# MPU_12x12.net
KiCad netlist of a schematic drawn in Altium Designer
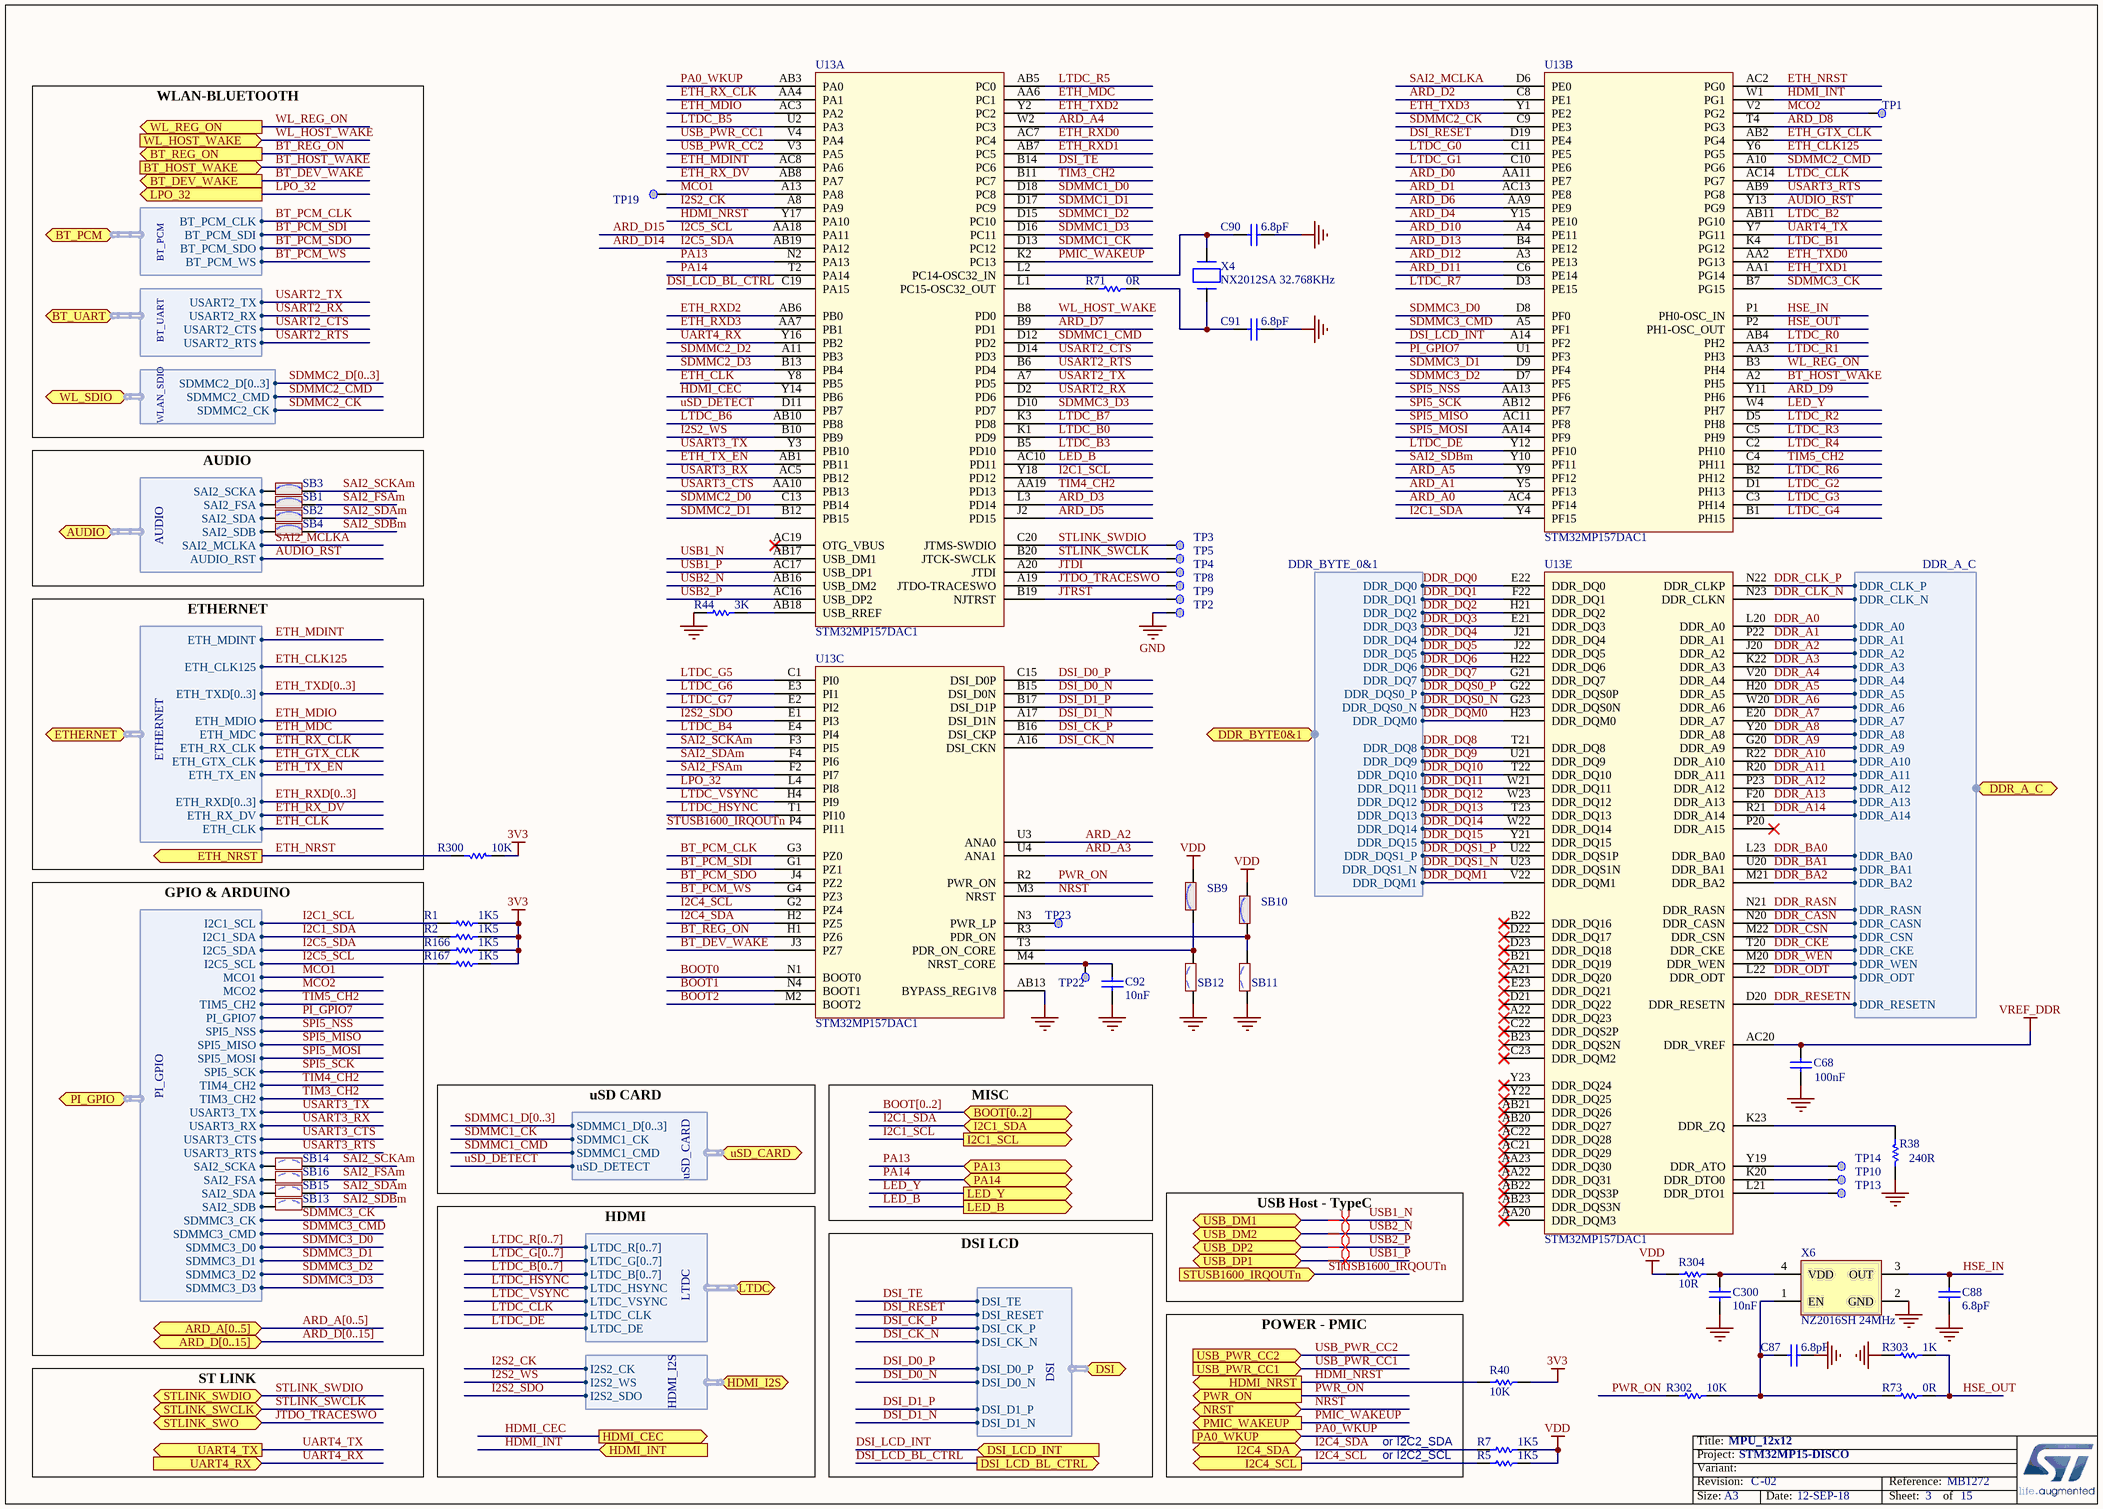
[diagram p0: MPU_12x12.SchDoc]

(export (version "E")
  (design (tool "Eeschema 10.0.6"))
  (components
    (comp (ref "C68")
      (value "100nF")
      (footprint "C0402")
      (description "Capacitor,100nF,16V,X7R,10%,0402")
      (fields
        (field (name "INTERNAL_PART_NUMBER") "MCD-00006")
        (field (name "MANUFACTURER_PART_NUMBER") "CC0402KRX7R7BB104")
        (field (name "PROVIDED_BY") "SUBCO")
      )
      (libsource (lib "MCD_PARTS_database") (part "Capacitor"))
    )
    (comp (ref "C87")
      (value "6.8pF")
      (footprint "C0402")
      (description "Capacitor, MLCC, 6.8pF, 50V, NPO, +-0.25pF, 0402, T=0.5mm")
      (fields
        (field (name "INTERNAL_PART_NUMBER") "MCD-00674")
        (field (name "MANUFACTURER_PART_NUMBER") "CC0402CRNPO9BN6R8")
        (field (name "PROVIDED_BY") "SUBCO")
      )
      (libsource (lib "MCD_PARTS_database") (part "Capacitor"))
    )
    (comp (ref "C88")
      (value "6.8pF")
      (footprint "C0402")
      (description "Capacitor, MLCC, 6.8pF, 50V, NPO, +-0.25pF, 0402, T=0.5mm")
      (fields
        (field (name "INTERNAL_PART_NUMBER") "MCD-00674")
        (field (name "MANUFACTURER_PART_NUMBER") "CC0402CRNPO9BN6R8")
        (field (name "PROVIDED_BY") "SUBCO")
      )
      (libsource (lib "MCD_PARTS_database") (part "Capacitor"))
    )
    (comp (ref "C90")
      (value "6.8pF")
      (footprint "C0402")
      (description "Capacitor, MLCC, 6.8pF, 50V, NPO, +-0.25pF, 0402, T=0.5mm")
      (fields
        (field (name "INTERNAL_PART_NUMBER") "MCD-00674")
        (field (name "MANUFACTURER_PART_NUMBER") "CC0402CRNPO9BN6R8")
        (field (name "PROVIDED_BY") "SUBCO")
      )
      (libsource (lib "MCD_PARTS_database") (part "Capacitor"))
    )
    (comp (ref "C91")
      (value "6.8pF")
      (footprint "C0402")
      (description "Capacitor, MLCC, 6.8pF, 50V, NPO, +-0.25pF, 0402, T=0.5mm")
      (fields
        (field (name "INTERNAL_PART_NUMBER") "MCD-00674")
        (field (name "MANUFACTURER_PART_NUMBER") "CC0402CRNPO9BN6R8")
        (field (name "PROVIDED_BY") "SUBCO")
      )
      (libsource (lib "MCD_PARTS_database") (part "Capacitor"))
    )
    (comp (ref "C92")
      (value "10nF")
      (footprint "C0402")
      (description "Capacitor, MLCC, 10nF, 16V, X7R, 10%, 0402, T=0.5mm")
      (fields
        (field (name "INTERNAL_PART_NUMBER") "MCD-00011")
        (field (name "MANUFACTURER_PART_NUMBER") "CC0402KRX7R7BB103")
        (field (name "PROVIDED_BY") "SUBCO")
      )
      (libsource (lib "MCD_PARTS_database") (part "Capacitor"))
    )
    (comp (ref "C300")
      (value "10nF")
      (footprint "C0402")
      (description "Capacitor, MLCC, 10nF, 16V, X7R, 10%, 0402, T=0.5mm")
      (fields
        (field (name "INTERNAL_PART_NUMBER") "MCD-00011")
        (field (name "MANUFACTURER_PART_NUMBER") "CC0402KRX7R7BB103")
        (field (name "PROVIDED_BY") "SUBCO")
      )
      (libsource (lib "MCD_PARTS_database") (part "Capacitor"))
    )
    (comp (ref "R1")
      (value "1K5")
      (footprint "R0402")
      (description "Resistor,1K5,0402,1%,1/16W")
      (fields
        (field (name "INTERNAL_PART_NUMBER") "MCD-00068")
        (field (name "MANUFACTURER_PART_NUMBER") "RC0402FR-071K5L")
        (field (name "PROVIDED_BY") "SUBCO")
      )
      (libsource (lib "MCD_PARTS_database") (part "Resistor"))
    )
    (comp (ref "R2")
      (value "1K5")
      (footprint "R0402")
      (description "Resistor,1K5,0402,1%,1/16W")
      (fields
        (field (name "INTERNAL_PART_NUMBER") "MCD-00068")
        (field (name "MANUFACTURER_PART_NUMBER") "RC0402FR-071K5L")
        (field (name "PROVIDED_BY") "SUBCO")
      )
      (libsource (lib "MCD_PARTS_database") (part "Resistor"))
    )
    (comp (ref "R5")
      (value "1K5")
      (footprint "R0402")
      (description "Resistor,1K5,0402,1%,1/16W")
      (fields
        (field (name "INTERNAL_PART_NUMBER") "MCD-00068")
        (field (name "MANUFACTURER_PART_NUMBER") "RC0402FR-071K5L")
        (field (name "PROVIDED_BY") "SUBCO")
      )
      (libsource (lib "MCD_PARTS_database") (part "Resistor"))
    )
    (comp (ref "R7")
      (value "1K5")
      (footprint "R0402")
      (description "Resistor,1K5,0402,1%,1/16W")
      (fields
        (field (name "INTERNAL_PART_NUMBER") "MCD-00068")
        (field (name "MANUFACTURER_PART_NUMBER") "RC0402FR-071K5L")
        (field (name "PROVIDED_BY") "SUBCO")
      )
      (libsource (lib "MCD_PARTS_database") (part "Resistor"))
    )
    (comp (ref "R38")
      (value "240R")
      (footprint "R0402")
      (description "Resistor,240R,0402,1%,1/16W")
      (fields
        (field (name "INTERNAL_PART_NUMBER") "MCD-00120")
        (field (name "MANUFACTURER_PART_NUMBER") "RC0402FR-07240RL")
        (field (name "PROVIDED_BY") "SUBCO")
      )
      (libsource (lib "MCD_PARTS_database") (part "Resistor"))
    )
    (comp (ref "R40")
      (value "10K")
      (footprint "R0402")
      (description "Resistor,10K,0402,1%,1/16W")
      (fields
        (field (name "INTERNAL_PART_NUMBER") "MCD-00053")
        (field (name "MANUFACTURER_PART_NUMBER") "RC0402FR-0710KL")
        (field (name "PROVIDED_BY") "SUBCO")
      )
      (libsource (lib "MCD_PARTS_database") (part "Resistor"))
    )
    (comp (ref "R44")
      (value "3K")
      (footprint "R0402")
      (description "Resistor,3K,0402,1%,1/16W")
      (fields
        (field (name "INTERNAL_PART_NUMBER") "MCD-00185")
        (field (name "MANUFACTURER_PART_NUMBER") "RC0402FR-073KL")
        (field (name "PROVIDED_BY") "SUBCO")
      )
      (libsource (lib "MCD_PARTS_database") (part "Resistor"))
    )
    (comp (ref "R71")
      (value "0R")
      (footprint "R0402")
      (description "Resistor,0R,0402,5%,1/16W")
      (fields
        (field (name "INTERNAL_PART_NUMBER") "MCD-00052")
        (field (name "MANUFACTURER_PART_NUMBER") "RC0402JR-070RL")
        (field (name "PROVIDED_BY") "SUBCO")
      )
      (libsource (lib "MCD_PARTS_database") (part "Resistor"))
    )
    (comp (ref "R73")
      (value "0R")
      (footprint "R0402")
      (description "Resistor,0R,0402,5%,1/16W")
      (fields
        (field (name "INTERNAL_PART_NUMBER") "MCD-00052")
        (field (name "MANUFACTURER_PART_NUMBER") "RC0402JR-070RL")
        (field (name "PROVIDED_BY") "SUBCO")
      )
      (libsource (lib "MCD_PARTS_database") (part "Resistor"))
    )
    (comp (ref "R166")
      (value "1K5")
      (footprint "R0402")
      (description "Resistor,1K5,0402,1%,1/16W")
      (fields
        (field (name "INTERNAL_PART_NUMBER") "MCD-00068")
        (field (name "MANUFACTURER_PART_NUMBER") "RC0402FR-071K5L")
        (field (name "PROVIDED_BY") "SUBCO")
      )
      (libsource (lib "MCD_PARTS_database") (part "Resistor"))
    )
    (comp (ref "R167")
      (value "1K5")
      (footprint "R0402")
      (description "Resistor,1K5,0402,1%,1/16W")
      (fields
        (field (name "INTERNAL_PART_NUMBER") "MCD-00068")
        (field (name "MANUFACTURER_PART_NUMBER") "RC0402FR-071K5L")
        (field (name "PROVIDED_BY") "SUBCO")
      )
      (libsource (lib "MCD_PARTS_database") (part "Resistor"))
    )
    (comp (ref "R300")
      (value "10K")
      (footprint "R0402")
      (description "Resistor,10K,0402,1%,1/16W")
      (fields
        (field (name "INTERNAL_PART_NUMBER") "MCD-00053")
        (field (name "MANUFACTURER_PART_NUMBER") "RC0402FR-0710KL")
        (field (name "PROVIDED_BY") "SUBCO")
      )
      (libsource (lib "MCD_PARTS_database") (part "Resistor"))
    )
    (comp (ref "R302")
      (value "10K")
      (footprint "R0402")
      (description "Resistor,10K,0402,1%,1/16W")
      (fields
        (field (name "INTERNAL_PART_NUMBER") "MCD-00053")
        (field (name "MANUFACTURER_PART_NUMBER") "RC0402FR-0710KL")
        (field (name "PROVIDED_BY") "SUBCO")
      )
      (libsource (lib "MCD_PARTS_database") (part "Resistor"))
    )
    (comp (ref "R303")
      (value "1K")
      (footprint "R0402")
      (description "Resistor,1K,0402,1%,1/16W")
      (fields
        (field (name "INTERNAL_PART_NUMBER") "MCD-00061")
        (field (name "MANUFACTURER_PART_NUMBER") "RC0402FR-071KL")
        (field (name "PROVIDED_BY") "SUBCO")
      )
      (libsource (lib "MCD_PARTS_database") (part "Resistor"))
    )
    (comp (ref "R304")
      (value "10R")
      (footprint "R0402")
      (description "Resistor,10R,0402,1%,1/16W")
      (fields
        (field (name "INTERNAL_PART_NUMBER") "MCD-00358")
        (field (name "MANUFACTURER_PART_NUMBER") "RC0402FR-0710RL")
        (field (name "PROVIDED_BY") "SUBCO")
      )
      (libsource (lib "MCD_PARTS_database") (part "Resistor"))
    )
    (comp (ref "SB1")
      (value "~")
      (footprint "SOLDER-BRIDGE_R0603-0R")
      (description "Solder Bridge ON")
      (fields
        (field (name "INTERNAL_PART_NUMBER") "MCD-00071")
        (field (name "MANUFACTURER") "YAGEO")
        (field (name "PROVIDED_BY") "SUBCO")
      )
      (libsource (lib "") (part "SB_ON_1"))
    )
    (comp (ref "SB2")
      (value "~")
      (footprint "SOLDER-BRIDGE_R0603-0R")
      (description "Solder Bridge ON")
      (fields
        (field (name "INTERNAL_PART_NUMBER") "MCD-00071")
        (field (name "MANUFACTURER") "YAGEO")
        (field (name "PROVIDED_BY") "SUBCO")
      )
      (libsource (lib "") (part "SB_ON_1"))
    )
    (comp (ref "SB3")
      (value "~")
      (footprint "SOLDER-BRIDGE_R0603-0R")
      (description "Solder Bridge ON")
      (fields
        (field (name "INTERNAL_PART_NUMBER") "MCD-00071")
        (field (name "MANUFACTURER") "YAGEO")
        (field (name "PROVIDED_BY") "SUBCO")
      )
      (libsource (lib "") (part "SB_ON_1"))
    )
    (comp (ref "SB4")
      (value "~")
      (footprint "SOLDER-BRIDGE_R0603-0R")
      (description "Solder Bridge ON")
      (fields
        (field (name "INTERNAL_PART_NUMBER") "MCD-00071")
        (field (name "MANUFACTURER") "YAGEO")
        (field (name "PROVIDED_BY") "SUBCO")
      )
      (libsource (lib "") (part "SB_ON_1"))
    )
    (comp (ref "SB9")
      (value "~")
      (footprint "SOLDER-BRIDGE_R0603-0R")
      (description "Solder Bridge ON")
      (fields
        (field (name "INTERNAL_PART_NUMBER") "MCD-00071")
        (field (name "MANUFACTURER") "YAGEO")
        (field (name "PROVIDED_BY") "SUBCO")
      )
      (libsource (lib "MCD_PARTS_database") (part "SB_ON"))
    )
    (comp (ref "SB10")
      (value "~")
      (footprint "SOLDER-BRIDGE_R0603-0R")
      (description "Solder Bridge ON")
      (fields
        (field (name "INTERNAL_PART_NUMBER") "MCD-00071")
        (field (name "MANUFACTURER") "YAGEO")
        (field (name "PROVIDED_BY") "SUBCO")
      )
      (libsource (lib "MCD_PARTS_database") (part "SB_ON"))
    )
    (comp (ref "SB11")
      (value "~")
      (footprint "SOLDER-BRIDGE_R0603-0R")
      (description "Solder Bridge OFF")
      (fields
        (field (name "INTERNAL_PART_NUMBER") "MCD-00072")
        (field (name "MANUFACTURER") "YAGEO")
        (field (name "PROVIDED_BY") "SUBCO")
      )
      (libsource (lib "") (part "SB_OFF_1"))
    )
    (comp (ref "SB12")
      (value "~")
      (footprint "SOLDER-BRIDGE_R0603-0R")
      (description "Solder Bridge OFF")
      (fields
        (field (name "INTERNAL_PART_NUMBER") "MCD-00072")
        (field (name "MANUFACTURER") "YAGEO")
        (field (name "PROVIDED_BY") "SUBCO")
      )
      (libsource (lib "") (part "SB_OFF_1"))
    )
    (comp (ref "SB13")
      (value "~")
      (footprint "SOLDER-BRIDGE_R0603-0R")
      (description "Solder Bridge OFF")
      (fields
        (field (name "INTERNAL_PART_NUMBER") "MCD-00072")
        (field (name "MANUFACTURER") "YAGEO")
        (field (name "PROVIDED_BY") "SUBCO")
      )
      (libsource (lib "MCD_PARTS_database") (part "SB_OFF"))
    )
    (comp (ref "SB14")
      (value "~")
      (footprint "SOLDER-BRIDGE_R0603-0R")
      (description "Solder Bridge OFF")
      (fields
        (field (name "INTERNAL_PART_NUMBER") "MCD-00072")
        (field (name "MANUFACTURER") "YAGEO")
        (field (name "PROVIDED_BY") "SUBCO")
      )
      (libsource (lib "MCD_PARTS_database") (part "SB_OFF"))
    )
    (comp (ref "SB15")
      (value "~")
      (footprint "SOLDER-BRIDGE_R0603-0R")
      (description "Solder Bridge OFF")
      (fields
        (field (name "INTERNAL_PART_NUMBER") "MCD-00072")
        (field (name "MANUFACTURER") "YAGEO")
        (field (name "PROVIDED_BY") "SUBCO")
      )
      (libsource (lib "MCD_PARTS_database") (part "SB_OFF"))
    )
    (comp (ref "SB16")
      (value "~")
      (footprint "SOLDER-BRIDGE_R0603-0R")
      (description "Solder Bridge OFF")
      (fields
        (field (name "INTERNAL_PART_NUMBER") "MCD-00072")
        (field (name "MANUFACTURER") "YAGEO")
        (field (name "PROVIDED_BY") "SUBCO")
      )
      (libsource (lib "MCD_PARTS_database") (part "SB_OFF"))
    )
    (comp (ref "TP1")
      (value "Test Point")
      (footprint "TP_SMD_1MM")
      (description "Test Point 1mm")
      (fields
        (field (name "INTERNAL_PART_NUMBER") "MCD-00074")
        (field (name "MANUFACTURER_PART_NUMBER") "n/a")
      )
      (libsource (lib "MCD_PARTS_database") (part "Test Point"))
    )
    (comp (ref "TP2")
      (value "Test Point")
      (footprint "TP_SMD_1MM")
      (description "Test Point 1mm")
      (fields
        (field (name "INTERNAL_PART_NUMBER") "MCD-00074")
        (field (name "MANUFACTURER_PART_NUMBER") "n/a")
      )
      (libsource (lib "MCD_PARTS_database") (part "Test Point"))
    )
    (comp (ref "TP3")
      (value "Test Point")
      (footprint "TP_SMD_1MM")
      (description "Test Point 1mm")
      (fields
        (field (name "INTERNAL_PART_NUMBER") "MCD-00074")
        (field (name "MANUFACTURER_PART_NUMBER") "n/a")
      )
      (libsource (lib "MCD_PARTS_database") (part "Test Point"))
    )
    (comp (ref "TP4")
      (value "Test Point")
      (footprint "TP_SMD_1MM")
      (description "Test Point 1mm")
      (fields
        (field (name "INTERNAL_PART_NUMBER") "MCD-00074")
        (field (name "MANUFACTURER_PART_NUMBER") "n/a")
      )
      (libsource (lib "MCD_PARTS_database") (part "Test Point"))
    )
    (comp (ref "TP5")
      (value "Test Point")
      (footprint "TP_SMD_1MM")
      (description "Test Point 1mm")
      (fields
        (field (name "INTERNAL_PART_NUMBER") "MCD-00074")
        (field (name "MANUFACTURER_PART_NUMBER") "n/a")
      )
      (libsource (lib "MCD_PARTS_database") (part "Test Point"))
    )
    (comp (ref "TP8")
      (value "Test Point")
      (footprint "TP_SMD_1MM")
      (description "Test Point 1mm")
      (fields
        (field (name "INTERNAL_PART_NUMBER") "MCD-00074")
        (field (name "MANUFACTURER_PART_NUMBER") "n/a")
      )
      (libsource (lib "MCD_PARTS_database") (part "Test Point"))
    )
    (comp (ref "TP9")
      (value "Test Point")
      (footprint "TP_SMD_1MM")
      (description "Test Point 1mm")
      (fields
        (field (name "INTERNAL_PART_NUMBER") "MCD-00074")
        (field (name "MANUFACTURER_PART_NUMBER") "n/a")
      )
      (libsource (lib "MCD_PARTS_database") (part "Test Point"))
    )
    (comp (ref "TP10")
      (value "~")
      (footprint "TP_SMD_0-6MM")
      (description "Test Point 0.6mm")
      (fields (field (name "INTERNAL_PART_NUMBER") "MCD-00631"))
      (libsource (lib "MCD_PARTS_database") (part "Test Point"))
    )
    (comp (ref "TP13")
      (value "~")
      (footprint "TP_SMD_0-6MM")
      (description "Test Point 0.6mm")
      (fields (field (name "INTERNAL_PART_NUMBER") "MCD-00631"))
      (libsource (lib "MCD_PARTS_database") (part "Test Point"))
    )
    (comp (ref "TP14")
      (value "~")
      (footprint "TP_SMD_0-6MM")
      (description "Test Point 0.6mm")
      (fields (field (name "INTERNAL_PART_NUMBER") "MCD-00631"))
      (libsource (lib "MCD_PARTS_database") (part "Test Point"))
    )
    (comp (ref "TP19")
      (value "Test Point")
      (footprint "TP_SMD_1MM")
      (description "Test Point 1mm")
      (fields
        (field (name "INTERNAL_PART_NUMBER") "MCD-00074")
        (field (name "MANUFACTURER_PART_NUMBER") "n/a")
      )
      (libsource (lib "") (part "Test Point_1"))
    )
    (comp (ref "TP22")
      (value "Test Point")
      (footprint "TP_SMD_1MM")
      (description "Test Point 1mm")
      (fields
        (field (name "INTERNAL_PART_NUMBER") "MCD-00074")
        (field (name "MANUFACTURER_PART_NUMBER") "n/a")
      )
      (libsource (lib "") (part "Test Point_2"))
    )
    (comp (ref "TP23")
      (value "Test Point")
      (footprint "TP_SMD_1MM")
      (description "Test Point 1mm")
      (fields
        (field (name "INTERNAL_PART_NUMBER") "MCD-00074")
        (field (name "MANUFACTURER_PART_NUMBER") "n/a")
      )
      (libsource (lib "MCD_PARTS_database") (part "Test Point"))
    )
    (comp (ref "U13")
      (value "STM32MP157DAC1")
      (footprint "ICC_TFBGA361_12X12_STM32MP157CAC3_P050-065")
      (description "MPU TFBGA12x12 without crypto increased frequency")
      (fields
        (field (name "INTERNAL_PART_NUMBER") "MCD-02020")
        (field (name "MANUFACTURER") "STMICROELECTRONICS")
        (field (name "PROVIDED_BY") "SUBCO with ST control")
      )
      (libsource (lib "MCD_PARTS_database") (part "STM32MP157DAC1"))
    )
    (comp (ref "X4")
      (value "NX2012SA 32.768KHz")
      (footprint "CRY_NX2012SA_2P")
      (description "Crystal 32.768kHz, 6pF, -+20PPM, R=80K, SMD")
      (fields
        (field (name "INTERNAL_PART_NUMBER") "MCD-01479")
        (field (name "MANUFACTURER_PART_NUMBER") "NX2012SA 32.768KHz EXS00A-MU00527")
        (field (name "PROVIDED_BY") "SUBCO")
      )
      (libsource (lib "MCD_PARTS_database") (part "XTAL_2_PINS"))
    )
    (comp (ref "X6")
      (value "NZ2016SH 24MHz")
      (footprint "CRY_NZ2016SH_4P")
      (description "Oscillator 24Mhz, +-50ppm, Vcc:3.3V typ (1.62V min), square wave: [0.1Vcc;0.9Vcc], Enable pin")
      (fields
        (field (name "INTERNAL_PART_NUMBER") "MCD-01627")
        (field (name "MANUFACTURER_PART_NUMBER") "NZ2016SH 24MHz END4869F")
        (field (name "PROVIDED_BY") "SUBCO")
      )
      (libsource (lib "MCD_PARTS_database") (part "OSCILLATOR_4_PINS"))
    )
  )
  (nets
    (net (code "13") (name "/ARD_A0") (class "Default")
      (node (ref "U13") (pin "AC4") (pinfunction "PF14_AC4") (pintype "passive"))
    )
    (net (code "14") (name "/ARD_A1") (class "Default")
      (node (ref "U13") (pin "Y5") (pinfunction "PF13_Y5") (pintype "passive"))
    )
    (net (code "15") (name "/ARD_A2") (class "Default")
      (node (ref "U13") (pin "U3") (pinfunction "ANA0_U3") (pintype "passive"))
    )
    (net (code "16") (name "/ARD_A3") (class "Default")
      (node (ref "U13") (pin "U4") (pinfunction "ANA1_U4") (pintype "passive"))
    )
    (net (code "17") (name "/ARD_A4") (class "Default")
      (node (ref "U13") (pin "W2") (pinfunction "PC3_W2") (pintype "passive"))
    )
    (net (code "18") (name "/ARD_A5") (class "Default")
      (node (ref "U13") (pin "Y9") (pinfunction "PF12_Y9") (pintype "passive"))
    )
    (net (code "20") (name "/ARD_D0") (class "Default")
      (node (ref "U13") (pin "AA11") (pinfunction "PE7_AA11") (pintype "passive"))
    )
    (net (code "21") (name "/ARD_D1") (class "Default")
      (node (ref "U13") (pin "AC13") (pinfunction "PE8_AC13") (pintype "passive"))
    )
    (net (code "22") (name "/ARD_D2") (class "Default")
      (node (ref "U13") (pin "C8") (pinfunction "PE1_C8") (pintype "passive"))
    )
    (net (code "23") (name "/ARD_D3") (class "Default")
      (node (ref "U13") (pin "L3") (pinfunction "PD14_L3") (pintype "passive"))
    )
    (net (code "24") (name "/ARD_D4") (class "Default")
      (node (ref "U13") (pin "Y15") (pinfunction "PE10_Y15") (pintype "passive"))
    )
    (net (code "25") (name "/ARD_D5") (class "Default")
      (node (ref "U13") (pin "J2") (pinfunction "PD15_J2") (pintype "passive"))
    )
    (net (code "26") (name "/ARD_D6") (class "Default")
      (node (ref "U13") (pin "AA9") (pinfunction "PE9_AA9") (pintype "passive"))
    )
    (net (code "27") (name "/ARD_D7") (class "Default")
      (node (ref "U13") (pin "B9") (pinfunction "PD1_B9") (pintype "passive"))
    )
    (net (code "28") (name "/ARD_D8") (class "Default")
      (node (ref "U13") (pin "T4") (pinfunction "PG3_T4") (pintype "passive"))
    )
    (net (code "29") (name "/ARD_D9") (class "Default")
      (node (ref "U13") (pin "Y11") (pinfunction "PH6_Y11") (pintype "passive"))
    )
    (net (code "30") (name "/ARD_D10") (class "Default")
      (node (ref "U13") (pin "A4") (pinfunction "PE11_A4") (pintype "passive"))
    )
    (net (code "31") (name "/ARD_D11") (class "Default")
      (node (ref "U13") (pin "C6") (pinfunction "PE14_C6") (pintype "passive"))
    )
    (net (code "32") (name "/ARD_D12") (class "Default")
      (node (ref "U13") (pin "A3") (pinfunction "PE13_A3") (pintype "passive"))
    )
    (net (code "33") (name "/ARD_D13") (class "Default")
      (node (ref "U13") (pin "B4") (pinfunction "PE12_B4") (pintype "passive"))
    )
    (net (code "34") (name "/ARD_D14") (class "Default")
      (node (ref "R166") (pin "2") (pinfunction "2_2") (pintype "passive"))
      (node (ref "U13") (pin "AB19") (pinfunction "PA12_AB19") (pintype "passive"))
    )
    (net (code "35") (name "/ARD_D15") (class "Default")
      (node (ref "R167") (pin "2") (pinfunction "2_2") (pintype "passive"))
      (node (ref "U13") (pin "AA18") (pinfunction "PA11_AA18") (pintype "passive"))
    )
    (net (code "37") (name "/AUDIO_RST") (class "Default")
      (node (ref "U13") (pin "Y13") (pinfunction "PG9_Y13") (pintype "passive"))
    )
    (net (code "38") (name "/BOOT0") (class "Default")
      (node (ref "U13") (pin "N1") (pinfunction "BOOT0_N1") (pintype "passive"))
    )
    (net (code "39") (name "/BOOT1") (class "Default")
      (node (ref "U13") (pin "N4") (pinfunction "BOOT1_N4") (pintype "passive"))
    )
    (net (code "40") (name "/BOOT2") (class "Default")
      (node (ref "U13") (pin "M2") (pinfunction "BOOT2_M2") (pintype "passive"))
    )
    (net (code "42") (name "/BT_DEV_WAKE") (class "Default")
      (node (ref "U13") (pin "J3") (pinfunction "PZ7_J3") (pintype "passive"))
    )
    (net (code "43") (name "/BT_HOST_WAKE") (class "Default")
      (node (ref "U13") (pin "A2") (pinfunction "PH5_A2") (pintype "passive"))
    )
    (net (code "44") (name "/BT_PCM_CLK") (class "Default")
      (node (ref "U13") (pin "G3") (pinfunction "PZ0_G3") (pintype "passive"))
    )
    (net (code "45") (name "/BT_PCM_SDI") (class "Default")
      (node (ref "U13") (pin "G1") (pinfunction "PZ1_G1") (pintype "passive"))
    )
    (net (code "46") (name "/BT_PCM_SDO") (class "Default")
      (node (ref "U13") (pin "J4") (pinfunction "PZ2_J4") (pintype "passive"))
    )
    (net (code "47") (name "/BT_PCM_WS") (class "Default")
      (node (ref "U13") (pin "G4") (pinfunction "PZ3_G4") (pintype "passive"))
    )
    (net (code "48") (name "/BT_REG_ON") (class "Default")
      (node (ref "U13") (pin "H1") (pinfunction "PZ6_H1") (pintype "passive"))
    )
    (net (code "49") (name "/DDR_A0") (class "Default")
      (node (ref "U13") (pin "L20") (pinfunction "DDR_A0_L20") (pintype "passive"))
    )
    (net (code "50") (name "/DDR_A1") (class "Default")
      (node (ref "U13") (pin "P22") (pinfunction "DDR_A1_P22") (pintype "passive"))
    )
    (net (code "51") (name "/DDR_A2") (class "Default")
      (node (ref "U13") (pin "J20") (pinfunction "DDR_A2_J20") (pintype "passive"))
    )
    (net (code "52") (name "/DDR_A3") (class "Default")
      (node (ref "U13") (pin "K22") (pinfunction "DDR_A3_K22") (pintype "passive"))
    )
    (net (code "53") (name "/DDR_A4") (class "Default")
      (node (ref "U13") (pin "V20") (pinfunction "DDR_A4_V20") (pintype "passive"))
    )
    (net (code "54") (name "/DDR_A5") (class "Default")
      (node (ref "U13") (pin "H20") (pinfunction "DDR_A5_H20") (pintype "passive"))
    )
    (net (code "55") (name "/DDR_A6") (class "Default")
      (node (ref "U13") (pin "W20") (pinfunction "DDR_A6_W20") (pintype "passive"))
    )
    (net (code "56") (name "/DDR_A7") (class "Default")
      (node (ref "U13") (pin "E20") (pinfunction "DDR_A7_E20") (pintype "passive"))
    )
    (net (code "57") (name "/DDR_A8") (class "Default")
      (node (ref "U13") (pin "Y20") (pinfunction "DDR_A8_Y20") (pintype "passive"))
    )
    (net (code "58") (name "/DDR_A9") (class "Default")
      (node (ref "U13") (pin "G20") (pinfunction "DDR_A9_G20") (pintype "passive"))
    )
    (net (code "59") (name "/DDR_A10") (class "Default")
      (node (ref "U13") (pin "R22") (pinfunction "DDR_A10_R22") (pintype "passive"))
    )
    (net (code "60") (name "/DDR_A11") (class "Default")
      (node (ref "U13") (pin "R20") (pinfunction "DDR_A11_R20") (pintype "passive"))
    )
    (net (code "61") (name "/DDR_A12") (class "Default")
      (node (ref "U13") (pin "P23") (pinfunction "DDR_A12_P23") (pintype "passive"))
    )
    (net (code "62") (name "/DDR_A13") (class "Default")
      (node (ref "U13") (pin "F20") (pinfunction "DDR_A13_F20") (pintype "passive"))
    )
    (net (code "63") (name "/DDR_A14") (class "Default")
      (node (ref "U13") (pin "R21") (pinfunction "DDR_A14_R21") (pintype "passive"))
    )
    (net (code "64") (name "/DDR_BA0") (class "Default")
      (node (ref "U13") (pin "L23") (pinfunction "DDR_BA0_L23") (pintype "passive"))
    )
    (net (code "65") (name "/DDR_BA1") (class "Default")
      (node (ref "U13") (pin "U20") (pinfunction "DDR_BA1_U20") (pintype "passive"))
    )
    (net (code "66") (name "/DDR_BA2") (class "Default")
      (node (ref "U13") (pin "M21") (pinfunction "DDR_BA2_M21") (pintype "passive"))
    )
    (net (code "67") (name "/DDR_CASN") (class "Default")
      (node (ref "U13") (pin "N20") (pinfunction "DDR_CASN_N20") (pintype "passive"))
    )
    (net (code "68") (name "/DDR_CKE") (class "Default")
      (node (ref "U13") (pin "T20") (pinfunction "DDR_CKE_T20") (pintype "passive"))
    )
    (net (code "69") (name "/DDR_CLK_N") (class "Default")
      (node (ref "U13") (pin "N23") (pinfunction "DDR_CLKN_N23") (pintype "passive"))
    )
    (net (code "70") (name "/DDR_CLK_P") (class "Default")
      (node (ref "U13") (pin "N22") (pinfunction "DDR_CLKP_N22") (pintype "passive"))
    )
    (net (code "71") (name "/DDR_CSN") (class "Default")
      (node (ref "U13") (pin "M22") (pinfunction "DDR_CSN_M22") (pintype "passive"))
    )
    (net (code "72") (name "/DDR_DQ0") (class "Default")
      (node (ref "U13") (pin "E22") (pinfunction "DDR_DQ0_E22") (pintype "passive"))
    )
    (net (code "73") (name "/DDR_DQ1") (class "Default")
      (node (ref "U13") (pin "F22") (pinfunction "DDR_DQ1_F22") (pintype "passive"))
    )
    (net (code "74") (name "/DDR_DQ2") (class "Default")
      (node (ref "U13") (pin "H21") (pinfunction "DDR_DQ2_H21") (pintype "passive"))
    )
    (net (code "75") (name "/DDR_DQ3") (class "Default")
      (node (ref "U13") (pin "E21") (pinfunction "DDR_DQ3_E21") (pintype "passive"))
    )
    (net (code "76") (name "/DDR_DQ4") (class "Default")
      (node (ref "U13") (pin "J21") (pinfunction "DDR_DQ4_J21") (pintype "passive"))
    )
    (net (code "77") (name "/DDR_DQ5") (class "Default")
      (node (ref "U13") (pin "J22") (pinfunction "DDR_DQ5_J22") (pintype "passive"))
    )
    (net (code "78") (name "/DDR_DQ6") (class "Default")
      (node (ref "U13") (pin "H22") (pinfunction "DDR_DQ6_H22") (pintype "passive"))
    )
    (net (code "79") (name "/DDR_DQ7") (class "Default")
      (node (ref "U13") (pin "G21") (pinfunction "DDR_DQ7_G21") (pintype "passive"))
    )
    (net (code "80") (name "/DDR_DQ8") (class "Default")
      (node (ref "U13") (pin "T21") (pinfunction "DDR_DQ8_T21") (pintype "passive"))
    )
    (net (code "81") (name "/DDR_DQ9") (class "Default")
      (node (ref "U13") (pin "U21") (pinfunction "DDR_DQ9_U21") (pintype "passive"))
    )
    (net (code "82") (name "/DDR_DQ10") (class "Default")
      (node (ref "U13") (pin "T22") (pinfunction "DDR_DQ10_T22") (pintype "passive"))
    )
    (net (code "83") (name "/DDR_DQ11") (class "Default")
      (node (ref "U13") (pin "W21") (pinfunction "DDR_DQ11_W21") (pintype "passive"))
    )
    (net (code "84") (name "/DDR_DQ12") (class "Default")
      (node (ref "U13") (pin "W23") (pinfunction "DDR_DQ12_W23") (pintype "passive"))
    )
    (net (code "85") (name "/DDR_DQ13") (class "Default")
      (node (ref "U13") (pin "T23") (pinfunction "DDR_DQ13_T23") (pintype "passive"))
    )
    (net (code "86") (name "/DDR_DQ14") (class "Default")
      (node (ref "U13") (pin "W22") (pinfunction "DDR_DQ14_W22") (pintype "passive"))
    )
    (net (code "87") (name "/DDR_DQ15") (class "Default")
      (node (ref "U13") (pin "Y21") (pinfunction "DDR_DQ15_Y21") (pintype "passive"))
    )
    (net (code "88") (name "/DDR_DQM0") (class "Default")
      (node (ref "U13") (pin "H23") (pinfunction "DDR_DQM0_H23") (pintype "passive"))
    )
    (net (code "89") (name "/DDR_DQM1") (class "Default")
      (node (ref "U13") (pin "V22") (pinfunction "DDR_DQM1_V22") (pintype "passive"))
    )
    (net (code "90") (name "/DDR_DQS0_N") (class "Default")
      (node (ref "U13") (pin "G23") (pinfunction "DDR_DQS0N_G23") (pintype "passive"))
    )
    (net (code "91") (name "/DDR_DQS0_P") (class "Default")
      (node (ref "U13") (pin "G22") (pinfunction "DDR_DQS0P_G22") (pintype "passive"))
    )
    (net (code "92") (name "/DDR_DQS1_N") (class "Default")
      (node (ref "U13") (pin "U23") (pinfunction "DDR_DQS1N_U23") (pintype "passive"))
    )
    (net (code "93") (name "/DDR_DQS1_P") (class "Default")
      (node (ref "U13") (pin "U22") (pinfunction "DDR_DQS1P_U22") (pintype "passive"))
    )
    (net (code "94") (name "/DDR_ODT") (class "Default")
      (node (ref "U13") (pin "L22") (pinfunction "DDR_ODT_L22") (pintype "passive"))
    )
    (net (code "95") (name "/DDR_RASN") (class "Default")
      (node (ref "U13") (pin "N21") (pinfunction "DDR_RASN_N21") (pintype "passive"))
    )
    (net (code "96") (name "/DDR_RESETN") (class "Default")
      (node (ref "U13") (pin "D20") (pinfunction "DDR_RESETN_D20") (pintype "passive"))
    )
    (net (code "97") (name "/DDR_WEN") (class "Default")
      (node (ref "U13") (pin "M20") (pinfunction "DDR_WEN_M20") (pintype "passive"))
    )
    (net (code "98") (name "/DSI_CK_N") (class "Default")
      (node (ref "U13") (pin "A16") (pinfunction "DSI_CKN_A16") (pintype "passive"))
    )
    (net (code "99") (name "/DSI_CK_P") (class "Default")
      (node (ref "U13") (pin "B16") (pinfunction "DSI_CKP_B16") (pintype "passive"))
    )
    (net (code "100") (name "/DSI_D0_N") (class "Default")
      (node (ref "U13") (pin "B15") (pinfunction "DSI_D0N_B15") (pintype "passive"))
    )
    (net (code "101") (name "/DSI_D0_P") (class "Default")
      (node (ref "U13") (pin "C15") (pinfunction "DSI_D0P_C15") (pintype "passive"))
    )
    (net (code "102") (name "/DSI_D1_N") (class "Default")
      (node (ref "U13") (pin "A17") (pinfunction "DSI_D1N_A17") (pintype "passive"))
    )
    (net (code "103") (name "/DSI_D1_P") (class "Default")
      (node (ref "U13") (pin "B17") (pinfunction "DSI_D1P_B17") (pintype "passive"))
    )
    (net (code "104") (name "/DSI_LCD_BL_CTRL") (class "Default")
      (node (ref "U13") (pin "C19") (pinfunction "PA15_C19") (pintype "passive"))
    )
    (net (code "105") (name "/DSI_LCD_INT") (class "Default")
      (node (ref "U13") (pin "A14") (pinfunction "PF2_A14") (pintype "passive"))
    )
    (net (code "106") (name "/DSI_RESET") (class "Default")
      (node (ref "U13") (pin "D19") (pinfunction "PE4_D19") (pintype "passive"))
    )
    (net (code "107") (name "/DSI_TE") (class "Default")
      (node (ref "U13") (pin "B14") (pinfunction "PC6_B14") (pintype "passive"))
    )
    (net (code "109") (name "/ETH_CLK") (class "Default")
      (node (ref "U13") (pin "Y8") (pinfunction "PB5_Y8") (pintype "passive"))
    )
    (net (code "110") (name "/ETH_CLK125") (class "Default")
      (node (ref "U13") (pin "Y6") (pinfunction "PG5_Y6") (pintype "passive"))
    )
    (net (code "111") (name "/ETH_GTX_CLK") (class "Default")
      (node (ref "U13") (pin "AB2") (pinfunction "PG4_AB2") (pintype "passive"))
    )
    (net (code "112") (name "/ETH_MDC") (class "Default")
      (node (ref "U13") (pin "AA6") (pinfunction "PC1_AA6") (pintype "passive"))
    )
    (net (code "113") (name "/ETH_MDINT") (class "Default")
      (node (ref "U13") (pin "AC8") (pinfunction "PA6_AC8") (pintype "passive"))
    )
    (net (code "114") (name "/ETH_MDIO") (class "Default")
      (node (ref "U13") (pin "AC3") (pinfunction "PA2_AC3") (pintype "passive"))
    )
    (net (code "115") (name "/ETH_NRST") (class "Default")
      (node (ref "R300") (pin "2") (pinfunction "2_2") (pintype "passive"))
      (node (ref "U13") (pin "AC2") (pinfunction "PG0_AC2") (pintype "passive"))
    )
    (net (code "116") (name "/ETH_RXD0") (class "Default")
      (node (ref "U13") (pin "AC7") (pinfunction "PC4_AC7") (pintype "passive"))
    )
    (net (code "117") (name "/ETH_RXD1") (class "Default")
      (node (ref "U13") (pin "AB7") (pinfunction "PC5_AB7") (pintype "passive"))
    )
    (net (code "118") (name "/ETH_RXD2") (class "Default")
      (node (ref "U13") (pin "AB6") (pinfunction "PB0_AB6") (pintype "passive"))
    )
    (net (code "119") (name "/ETH_RXD3") (class "Default")
      (node (ref "U13") (pin "AA7") (pinfunction "PB1_AA7") (pintype "passive"))
    )
    (net (code "120") (name "/ETH_RX_CLK") (class "Default")
      (node (ref "U13") (pin "AA4") (pinfunction "PA1_AA4") (pintype "passive"))
    )
    (net (code "121") (name "/ETH_RX_DV") (class "Default")
      (node (ref "U13") (pin "AB8") (pinfunction "PA7_AB8") (pintype "passive"))
    )
    (net (code "122") (name "/ETH_TXD0") (class "Default")
      (node (ref "U13") (pin "AA2") (pinfunction "PG13_AA2") (pintype "passive"))
    )
    (net (code "123") (name "/ETH_TXD1") (class "Default")
      (node (ref "U13") (pin "AA1") (pinfunction "PG14_AA1") (pintype "passive"))
    )
    (net (code "124") (name "/ETH_TXD2") (class "Default")
      (node (ref "U13") (pin "Y2") (pinfunction "PC2_Y2") (pintype "passive"))
    )
    (net (code "125") (name "/ETH_TXD3") (class "Default")
      (node (ref "U13") (pin "Y1") (pinfunction "PE2_Y1") (pintype "passive"))
    )
    (net (code "127") (name "/ETH_TX_EN") (class "Default")
      (node (ref "U13") (pin "AB1") (pinfunction "PB11_AB1") (pintype "passive"))
    )
    (net (code "128") (name "/HDMI_CEC") (class "Default")
      (node (ref "U13") (pin "Y14") (pinfunction "PB6_Y14") (pintype "passive"))
    )
    (net (code "129") (name "/HDMI_INT") (class "Default")
      (node (ref "U13") (pin "W1") (pinfunction "PG1_W1") (pintype "passive"))
    )
    (net (code "130") (name "/HDMI_NRST") (class "Default")
      (node (ref "R40") (pin "2") (pinfunction "2_2") (pintype "passive"))
      (node (ref "U13") (pin "Y17") (pinfunction "PA10_Y17") (pintype "passive"))
    )
    (net (code "131") (name "/HSE_IN") (class "Default")
      (node (ref "C88") (pin "2") (pinfunction "2_2") (pintype "passive"))
      (node (ref "U13") (pin "P1") (pinfunction "PH0-OSC_IN_P1") (pintype "passive"))
      (node (ref "X6") (pin "3") (pinfunction "OUT_3") (pintype "passive"))
    )
    (net (code "132") (name "/HSE_OUT") (class "Default")
      (node (ref "R303") (pin "1") (pinfunction "1_1") (pintype "passive"))
      (node (ref "R73") (pin "2") (pinfunction "2_2") (pintype "passive"))
      (node (ref "U13") (pin "P2") (pinfunction "PH1-OSC_OUT_P2") (pintype "passive"))
    )
    (net (code "133") (name "/I2C1_SCL") (class "Default")
      (node (ref "R1") (pin "2") (pinfunction "2_2") (pintype "passive"))
      (node (ref "U13") (pin "Y18") (pinfunction "PD12_Y18") (pintype "passive"))
    )
    (net (code "134") (name "/I2C1_SDA") (class "Default")
      (node (ref "R2") (pin "2") (pinfunction "2_2") (pintype "passive"))
      (node (ref "U13") (pin "Y4") (pinfunction "PF15_Y4") (pintype "passive"))
    )
    (net (code "135") (name "/I2C4_SCL") (class "Default")
      (node (ref "R5") (pin "2") (pinfunction "2_2") (pintype "passive"))
      (node (ref "U13") (pin "G2") (pinfunction "PZ4_G2") (pintype "passive"))
    )
    (net (code "136") (name "/I2C4_SDA") (class "Default")
      (node (ref "R7") (pin "2") (pinfunction "2_2") (pintype "passive"))
      (node (ref "U13") (pin "H2") (pinfunction "PZ5_H2") (pintype "passive"))
    )
    (net (code "137") (name "/I2S2_CK") (class "Default")
      (node (ref "U13") (pin "A8") (pinfunction "PA9_A8") (pintype "passive"))
    )
    (net (code "138") (name "/I2S2_SDO") (class "Default")
      (node (ref "U13") (pin "E1") (pinfunction "PI3_E1") (pintype "passive"))
    )
    (net (code "139") (name "/I2S2_WS") (class "Default")
      (node (ref "U13") (pin "B10") (pinfunction "PB9_B10") (pintype "passive"))
    )
    (net (code "140") (name "/JTDI") (class "Default")
      (node (ref "TP4") (pin "1") (pinfunction "1_1") (pintype "passive"))
      (node (ref "U13") (pin "A20") (pinfunction "JTDI_A20") (pintype "passive"))
    )
    (net (code "141") (name "/JTDO_TRACESWO") (class "Default")
      (node (ref "TP8") (pin "1") (pinfunction "1_1") (pintype "passive"))
      (node (ref "U13") (pin "A19") (pinfunction "JTDO-TRACESWO_A19") (pintype "passive"))
    )
    (net (code "142") (name "/JTRST") (class "Default")
      (node (ref "TP9") (pin "1") (pinfunction "1_1") (pintype "passive"))
      (node (ref "U13") (pin "B19") (pinfunction "NJTRST_B19") (pintype "passive"))
    )
    (net (code "143") (name "/LED_B") (class "Default")
      (node (ref "U13") (pin "AC10") (pinfunction "PD11_AC10") (pintype "passive"))
    )
    (net (code "144") (name "/LED_Y") (class "Default")
      (node (ref "U13") (pin "W4") (pinfunction "PH7_W4") (pintype "passive"))
    )
    (net (code "145") (name "/LPO_32") (class "Default")
      (node (ref "U13") (pin "L4") (pinfunction "PI8_L4") (pintype "passive"))
    )
    (net (code "146") (name "/LTDC_B0") (class "Default")
      (node (ref "U13") (pin "K1") (pinfunction "PD9_K1") (pintype "passive"))
    )
    (net (code "147") (name "/LTDC_B1") (class "Default")
      (node (ref "U13") (pin "K4") (pinfunction "PG12_K4") (pintype "passive"))
    )
    (net (code "148") (name "/LTDC_B2") (class "Default")
      (node (ref "U13") (pin "AB11") (pinfunction "PG10_AB11") (pintype "passive"))
    )
    (net (code "149") (name "/LTDC_B3") (class "Default")
      (node (ref "U13") (pin "B5") (pinfunction "PD10_B5") (pintype "passive"))
    )
    (net (code "150") (name "/LTDC_B4") (class "Default")
      (node (ref "U13") (pin "E4") (pinfunction "PI4_E4") (pintype "passive"))
    )
    (net (code "151") (name "/LTDC_B5") (class "Default")
      (node (ref "U13") (pin "U2") (pinfunction "PA3_U2") (pintype "passive"))
    )
    (net (code "152") (name "/LTDC_B6") (class "Default")
      (node (ref "U13") (pin "AB10") (pinfunction "PB8_AB10") (pintype "passive"))
    )
    (net (code "153") (name "/LTDC_B7") (class "Default")
      (node (ref "U13") (pin "K3") (pinfunction "PD8_K3") (pintype "passive"))
    )
    (net (code "155") (name "/LTDC_CLK") (class "Default")
      (node (ref "U13") (pin "AC14") (pinfunction "PG7_AC14") (pintype "passive"))
    )
    (net (code "156") (name "/LTDC_DE") (class "Default")
      (node (ref "U13") (pin "Y12") (pinfunction "PF10_Y12") (pintype "passive"))
    )
    (net (code "157") (name "/LTDC_G0") (class "Default")
      (node (ref "U13") (pin "C11") (pinfunction "PE5_C11") (pintype "passive"))
    )
    (net (code "158") (name "/LTDC_G1") (class "Default")
      (node (ref "U13") (pin "C10") (pinfunction "PE6_C10") (pintype "passive"))
    )
    (net (code "159") (name "/LTDC_G2") (class "Default")
      (node (ref "U13") (pin "D1") (pinfunction "PH13_D1") (pintype "passive"))
    )
    (net (code "160") (name "/LTDC_G3") (class "Default")
      (node (ref "U13") (pin "C3") (pinfunction "PH14_C3") (pintype "passive"))
    )
    (net (code "161") (name "/LTDC_G4") (class "Default")
      (node (ref "U13") (pin "B1") (pinfunction "PH15_B1") (pintype "passive"))
    )
    (net (code "162") (name "/LTDC_G5") (class "Default")
      (node (ref "U13") (pin "C1") (pinfunction "PI0_C1") (pintype "passive"))
    )
    (net (code "163") (name "/LTDC_G6") (class "Default")
      (node (ref "U13") (pin "E3") (pinfunction "PI1_E3") (pintype "passive"))
    )
    (net (code "164") (name "/LTDC_G7") (class "Default")
      (node (ref "U13") (pin "E2") (pinfunction "PI2_E2") (pintype "passive"))
    )
    (net (code "166") (name "/LTDC_HSYNC") (class "Default")
      (node (ref "U13") (pin "T1") (pinfunction "PI10_T1") (pintype "passive"))
    )
    (net (code "167") (name "/LTDC_R0") (class "Default")
      (node (ref "U13") (pin "AB4") (pinfunction "PH2_AB4") (pintype "passive"))
    )
    (net (code "168") (name "/LTDC_R1") (class "Default")
      (node (ref "U13") (pin "AA3") (pinfunction "PH3_AA3") (pintype "passive"))
    )
    (net (code "169") (name "/LTDC_R2") (class "Default")
      (node (ref "U13") (pin "D5") (pinfunction "PH8_D5") (pintype "passive"))
    )
    (net (code "170") (name "/LTDC_R3") (class "Default")
      (node (ref "U13") (pin "C5") (pinfunction "PH9_C5") (pintype "passive"))
    )
    (net (code "171") (name "/LTDC_R4") (class "Default")
      (node (ref "U13") (pin "C2") (pinfunction "PH10_C2") (pintype "passive"))
    )
    (net (code "172") (name "/LTDC_R5") (class "Default")
      (node (ref "U13") (pin "AB5") (pinfunction "PC0_AB5") (pintype "passive"))
    )
    (net (code "173") (name "/LTDC_R6") (class "Default")
      (node (ref "U13") (pin "B2") (pinfunction "PH12_B2") (pintype "passive"))
    )
    (net (code "174") (name "/LTDC_R7") (class "Default")
      (node (ref "U13") (pin "D3") (pinfunction "PE15_D3") (pintype "passive"))
    )
    (net (code "176") (name "/LTDC_VSYNC") (class "Default")
      (node (ref "U13") (pin "H4") (pinfunction "PI9_H4") (pintype "passive"))
    )
    (net (code "177") (name "/MCO1") (class "Default")
      (node (ref "TP19") (pin "1") (pinfunction "1_1") (pintype "passive"))
      (node (ref "U13") (pin "A13") (pinfunction "PA8_A13") (pintype "passive"))
    )
    (net (code "178") (name "/MCO2") (class "Default")
      (node (ref "TP1") (pin "1") (pinfunction "1_1") (pintype "passive"))
      (node (ref "U13") (pin "V2") (pinfunction "PG2_V2") (pintype "passive"))
    )
    (net (code "179") (name "/NRST") (class "Default")
      (node (ref "U13") (pin "M3") (pinfunction "NRST_M3") (pintype "passive"))
    )
    (net (code "180") (name "/PA0_WKUP") (class "Default")
      (node (ref "U13") (pin "AB3") (pinfunction "PA0_AB3") (pintype "passive"))
    )
    (net (code "181") (name "/PA13") (class "Default")
      (node (ref "U13") (pin "N2") (pinfunction "PA13_N2") (pintype "passive"))
    )
    (net (code "182") (name "/PA14") (class "Default")
      (node (ref "U13") (pin "T2") (pinfunction "PA14_T2") (pintype "passive"))
    )
    (net (code "183") (name "/PI_GPIO7") (class "Default")
      (node (ref "U13") (pin "U1") (pinfunction "PF3_U1") (pintype "passive"))
    )
    (net (code "184") (name "/PMIC_WAKEUP") (class "Default")
      (node (ref "U13") (pin "K2") (pinfunction "PC13_K2") (pintype "passive"))
    )
    (net (code "185") (name "/PWR_ON") (class "Default")
      (node (ref "R302") (pin "2") (pinfunction "2_2") (pintype "passive"))
      (node (ref "U13") (pin "R2") (pinfunction "PWR_ON_R2") (pintype "passive"))
    )
    (net (code "186") (name "/SAI2_FSAm") (class "Default")
      (node (ref "SB1") (pin "2") (pinfunction "2_2") (pintype "passive"))
      (node (ref "SB16") (pin "2") (pinfunction "2_2") (pintype "passive"))
      (node (ref "U13") (pin "F2") (pinfunction "PI7_F2") (pintype "passive"))
    )
    (net (code "187") (name "/SAI2_MCLKA") (class "Default")
      (node (ref "U13") (pin "D6") (pinfunction "PE0_D6") (pintype "passive"))
    )
    (net (code "188") (name "/SAI2_SCKAm") (class "Default")
      (node (ref "SB14") (pin "2") (pinfunction "2_2") (pintype "passive"))
      (node (ref "SB3") (pin "2") (pinfunction "2_2") (pintype "passive"))
      (node (ref "U13") (pin "F3") (pinfunction "PI5_F3") (pintype "passive"))
    )
    (net (code "189") (name "/SAI2_SDAm") (class "Default")
      (node (ref "SB15") (pin "2") (pinfunction "2_2") (pintype "passive"))
      (node (ref "SB2") (pin "2") (pinfunction "2_2") (pintype "passive"))
      (node (ref "U13") (pin "F4") (pinfunction "PI6_F4") (pintype "passive"))
    )
    (net (code "190") (name "/SAI2_SDBm") (class "Default")
      (node (ref "SB13") (pin "2") (pinfunction "2_2") (pintype "passive"))
      (node (ref "SB4") (pin "2") (pinfunction "2_2") (pintype "passive"))
      (node (ref "U13") (pin "Y10") (pinfunction "PF11_Y10") (pintype "passive"))
    )
    (net (code "191") (name "/SDMMC1_CK") (class "Default")
      (node (ref "U13") (pin "D13") (pinfunction "PC12_D13") (pintype "passive"))
    )
    (net (code "192") (name "/SDMMC1_CMD") (class "Default")
      (node (ref "U13") (pin "D12") (pinfunction "PD2_D12") (pintype "passive"))
    )
    (net (code "193") (name "/SDMMC1_D0") (class "Default")
      (node (ref "U13") (pin "D18") (pinfunction "PC8_D18") (pintype "passive"))
    )
    (net (code "194") (name "/SDMMC1_D1") (class "Default")
      (node (ref "U13") (pin "D17") (pinfunction "PC9_D17") (pintype "passive"))
    )
    (net (code "195") (name "/SDMMC1_D2") (class "Default")
      (node (ref "U13") (pin "D15") (pinfunction "PC10_D15") (pintype "passive"))
    )
    (net (code "196") (name "/SDMMC1_D3") (class "Default")
      (node (ref "U13") (pin "D16") (pinfunction "PC11_D16") (pintype "passive"))
    )
    (net (code "198") (name "/SDMMC2_CK") (class "Default")
      (node (ref "U13") (pin "C9") (pinfunction "PE3_C9") (pintype "passive"))
    )
    (net (code "199") (name "/SDMMC2_CMD") (class "Default")
      (node (ref "U13") (pin "A10") (pinfunction "PG6_A10") (pintype "passive"))
    )
    (net (code "200") (name "/SDMMC2_D0") (class "Default")
      (node (ref "U13") (pin "C13") (pinfunction "PB14_C13") (pintype "passive"))
    )
    (net (code "201") (name "/SDMMC2_D1") (class "Default")
      (node (ref "U13") (pin "B12") (pinfunction "PB15_B12") (pintype "passive"))
    )
    (net (code "202") (name "/SDMMC2_D2") (class "Default")
      (node (ref "U13") (pin "A11") (pinfunction "PB3_A11") (pintype "passive"))
    )
    (net (code "203") (name "/SDMMC2_D3") (class "Default")
      (node (ref "U13") (pin "B13") (pinfunction "PB4_B13") (pintype "passive"))
    )
    (net (code "205") (name "/SDMMC3_CK") (class "Default")
      (node (ref "U13") (pin "B7") (pinfunction "PG15_B7") (pintype "passive"))
    )
    (net (code "206") (name "/SDMMC3_CMD") (class "Default")
      (node (ref "U13") (pin "A5") (pinfunction "PF1_A5") (pintype "passive"))
    )
    (net (code "207") (name "/SDMMC3_D0") (class "Default")
      (node (ref "U13") (pin "D8") (pinfunction "PF0_D8") (pintype "passive"))
    )
    (net (code "208") (name "/SDMMC3_D1") (class "Default")
      (node (ref "U13") (pin "D9") (pinfunction "PF4_D9") (pintype "passive"))
    )
    (net (code "209") (name "/SDMMC3_D2") (class "Default")
      (node (ref "U13") (pin "D7") (pinfunction "PF5_D7") (pintype "passive"))
    )
    (net (code "210") (name "/SDMMC3_D3") (class "Default")
      (node (ref "U13") (pin "D10") (pinfunction "PD7_D10") (pintype "passive"))
    )
    (net (code "211") (name "/SPI5_MISO") (class "Default")
      (node (ref "U13") (pin "AC11") (pinfunction "PF8_AC11") (pintype "passive"))
    )
    (net (code "212") (name "/SPI5_MOSI") (class "Default")
      (node (ref "U13") (pin "AA14") (pinfunction "PF9_AA14") (pintype "passive"))
    )
    (net (code "213") (name "/SPI5_NSS") (class "Default")
      (node (ref "U13") (pin "AA13") (pinfunction "PF6_AA13") (pintype "passive"))
    )
    (net (code "214") (name "/SPI5_SCK") (class "Default")
      (node (ref "U13") (pin "AB12") (pinfunction "PF7_AB12") (pintype "passive"))
    )
    (net (code "215") (name "/STLINK_SWCLK") (class "Default")
      (node (ref "TP5") (pin "1") (pinfunction "1_1") (pintype "passive"))
      (node (ref "U13") (pin "B20") (pinfunction "JTCK-SWCLK_B20") (pintype "passive"))
    )
    (net (code "216") (name "/STLINK_SWDIO") (class "Default")
      (node (ref "TP3") (pin "1") (pinfunction "1_1") (pintype "passive"))
      (node (ref "U13") (pin "C20") (pinfunction "JTMS-SWDIO_C20") (pintype "passive"))
    )
    (net (code "217") (name "/STUSB1600_IRQOUTn") (class "Default")
      (node (ref "U13") (pin "P4") (pinfunction "PI11_P4") (pintype "passive"))
    )
    (net (code "218") (name "/TIM3_CH2") (class "Default")
      (node (ref "U13") (pin "B11") (pinfunction "PC7_B11") (pintype "passive"))
    )
    (net (code "219") (name "/TIM4_CH2") (class "Default")
      (node (ref "U13") (pin "AA19") (pinfunction "PD13_AA19") (pintype "passive"))
    )
    (net (code "220") (name "/TIM5_CH2") (class "Default")
      (node (ref "U13") (pin "C4") (pinfunction "PH11_C4") (pintype "passive"))
    )
    (net (code "221") (name "/UART4_RX") (class "Default")
      (node (ref "U13") (pin "Y16") (pinfunction "PB2_Y16") (pintype "passive"))
    )
    (net (code "222") (name "/UART4_TX") (class "Default")
      (node (ref "U13") (pin "Y7") (pinfunction "PG11_Y7") (pintype "passive"))
    )
    (net (code "223") (name "/USART2_CTS") (class "Default")
      (node (ref "U13") (pin "D14") (pinfunction "PD3_D14") (pintype "passive"))
    )
    (net (code "224") (name "/USART2_RTS") (class "Default")
      (node (ref "U13") (pin "B6") (pinfunction "PD4_B6") (pintype "passive"))
    )
    (net (code "225") (name "/USART2_RX") (class "Default")
      (node (ref "U13") (pin "D2") (pinfunction "PD6_D2") (pintype "passive"))
    )
    (net (code "226") (name "/USART2_TX") (class "Default")
      (node (ref "U13") (pin "A7") (pinfunction "PD5_A7") (pintype "passive"))
    )
    (net (code "227") (name "/USART3_CTS") (class "Default")
      (node (ref "U13") (pin "AA10") (pinfunction "PB13_AA10") (pintype "passive"))
    )
    (net (code "228") (name "/USART3_RTS") (class "Default")
      (node (ref "U13") (pin "AB9") (pinfunction "PG8_AB9") (pintype "passive"))
    )
    (net (code "229") (name "/USART3_RX") (class "Default")
      (node (ref "U13") (pin "AC5") (pinfunction "PB12_AC5") (pintype "passive"))
    )
    (net (code "230") (name "/USART3_TX") (class "Default")
      (node (ref "U13") (pin "Y3") (pinfunction "PB10_Y3") (pintype "passive"))
    )
    (net (code "231") (name "/USB1_N") (class "Default")
      (node (ref "U13") (pin "AB17") (pinfunction "USB_DM1_AB17") (pintype "passive"))
    )
    (net (code "232") (name "/USB1_P") (class "Default")
      (node (ref "U13") (pin "AC17") (pinfunction "USB_DP1_AC17") (pintype "passive"))
    )
    (net (code "233") (name "/USB2_N") (class "Default")
      (node (ref "U13") (pin "AB16") (pinfunction "USB_DM2_AB16") (pintype "passive"))
    )
    (net (code "234") (name "/USB2_P") (class "Default")
      (node (ref "U13") (pin "AC16") (pinfunction "USB_DP2_AC16") (pintype "passive"))
    )
    (net (code "235") (name "/USB_PWR_CC1") (class "Default")
      (node (ref "U13") (pin "V4") (pinfunction "PA4_V4") (pintype "passive"))
    )
    (net (code "236") (name "/USB_PWR_CC2") (class "Default")
      (node (ref "U13") (pin "V3") (pinfunction "PA5_V3") (pintype "passive"))
    )
    (net (code "237") (name "/WL_HOST_WAKE") (class "Default")
      (node (ref "U13") (pin "B8") (pinfunction "PD0_B8") (pintype "passive"))
    )
    (net (code "238") (name "/WL_REG_ON") (class "Default")
      (node (ref "U13") (pin "B3") (pinfunction "PH4_B3") (pintype "passive"))
    )
    (net (code "239") (name "/uSD_DETECT") (class "Default")
      (node (ref "U13") (pin "D11") (pinfunction "PB7_D11") (pintype "passive"))
    )
    (net (code "252") (name "3V3") (class "Default")
      (node (ref "R1") (pin "1") (pinfunction "1_1") (pintype "passive"))
      (node (ref "R166") (pin "1") (pinfunction "1_1") (pintype "passive"))
      (node (ref "R167") (pin "1") (pinfunction "1_1") (pintype "passive"))
      (node (ref "R2") (pin "1") (pinfunction "1_1") (pintype "passive"))
      (node (ref "R300") (pin "1") (pinfunction "1_1") (pintype "passive"))
      (node (ref "R40") (pin "1") (pinfunction "1_1") (pintype "passive"))
    )
    (net (code "253") (name "GND") (class "Default")
      (node (ref "C300") (pin "1") (pinfunction "1_1") (pintype "passive"))
      (node (ref "C68") (pin "1") (pinfunction "1_1") (pintype "passive"))
      (node (ref "C87") (pin "2") (pinfunction "2_2") (pintype "passive"))
      (node (ref "C88") (pin "1") (pinfunction "1_1") (pintype "passive"))
      (node (ref "C90") (pin "2") (pinfunction "2_2") (pintype "passive"))
      (node (ref "C91") (pin "2") (pinfunction "2_2") (pintype "passive"))
      (node (ref "C92") (pin "1") (pinfunction "1_1") (pintype "passive"))
      (node (ref "R303") (pin "2") (pinfunction "2_2") (pintype "passive"))
      (node (ref "R38") (pin "2") (pinfunction "2_2") (pintype "passive"))
      (node (ref "R44") (pin "1") (pinfunction "1_1") (pintype "passive"))
      (node (ref "SB11") (pin "1") (pinfunction "1_1") (pintype "passive"))
      (node (ref "SB12") (pin "1") (pinfunction "1_1") (pintype "passive"))
      (node (ref "TP2") (pin "1") (pinfunction "1_1") (pintype "passive"))
      (node (ref "U13") (pin "AB13") (pinfunction "BYPASS_REG1V8_AB13") (pintype "passive"))
      (node (ref "X6") (pin "2") (pinfunction "GND_2") (pintype "passive"))
    )
    (net (code "254") (name "Net-(U13A-PC14-OSC32_IN)") (class "Default")
      (node (ref "C90") (pin "1") (pinfunction "1_1") (pintype "passive"))
      (node (ref "U13") (pin "L2") (pinfunction "PC14-OSC32_IN_L2") (pintype "passive"))
      (node (ref "X4") (pin "2") (pinfunction "X2_2") (pintype "passive"))
    )
    (net (code "255") (name "Net-(U13A-PC15-OSC32_OUT)") (class "Default")
      (node (ref "R71") (pin "1") (pinfunction "1_1") (pintype "passive"))
      (node (ref "U13") (pin "L1") (pinfunction "PC15-OSC32_OUT_L1") (pintype "passive"))
    )
    (net (code "256") (name "Net-(U13A-USB_RREF)") (class "Default")
      (node (ref "R44") (pin "2") (pinfunction "2_2") (pintype "passive"))
      (node (ref "U13") (pin "AB18") (pinfunction "USB_RREF_AB18") (pintype "passive"))
    )
    (net (code "257") (name "Net-(U13C-NRST_CORE)") (class "Default")
      (node (ref "C92") (pin "2") (pinfunction "2_2") (pintype "passive"))
      (node (ref "TP22") (pin "1") (pinfunction "1_1") (pintype "passive"))
      (node (ref "U13") (pin "M4") (pinfunction "NRST_CORE_M4") (pintype "passive"))
    )
    (net (code "258") (name "Net-(U13C-PDR_ON)") (class "Default")
      (node (ref "SB10") (pin "1") (pinfunction "1_1") (pintype "passive"))
      (node (ref "SB11") (pin "2") (pinfunction "2_2") (pintype "passive"))
      (node (ref "U13") (pin "R3") (pinfunction "PDR_ON_R3") (pintype "passive"))
    )
    (net (code "259") (name "Net-(U13C-PDR_ON_CORE)") (class "Default")
      (node (ref "SB12") (pin "2") (pinfunction "2_2") (pintype "passive"))
      (node (ref "SB9") (pin "1") (pinfunction "1_1") (pintype "passive"))
      (node (ref "U13") (pin "T3") (pinfunction "PDR_ON_CORE_T3") (pintype "passive"))
    )
    (net (code "260") (name "Net-(U13C-PWR_LP)") (class "Default")
      (node (ref "TP23") (pin "1") (pinfunction "1_1") (pintype "passive"))
      (node (ref "U13") (pin "N3") (pinfunction "PWR_LP_N3") (pintype "passive"))
    )
    (net (code "261") (name "Net-(U13E-DDR_ATO)") (class "Default")
      (node (ref "TP14") (pin "1") (pinfunction "1_1") (pintype "passive"))
      (node (ref "U13") (pin "Y19") (pinfunction "DDR_ATO_Y19") (pintype "passive"))
    )
    (net (code "262") (name "Net-(U13E-DDR_DTO0)") (class "Default")
      (node (ref "TP10") (pin "1") (pinfunction "1_1") (pintype "passive"))
      (node (ref "U13") (pin "K20") (pinfunction "DDR_DTO0_K20") (pintype "passive"))
    )
    (net (code "263") (name "Net-(U13E-DDR_DTO1)") (class "Default")
      (node (ref "TP13") (pin "1") (pinfunction "1_1") (pintype "passive"))
      (node (ref "U13") (pin "L21") (pinfunction "DDR_DTO1_L21") (pintype "passive"))
    )
    (net (code "264") (name "Net-(U13E-DDR_ZQ)") (class "Default")
      (node (ref "R38") (pin "1") (pinfunction "1_1") (pintype "passive"))
      (node (ref "U13") (pin "K23") (pinfunction "DDR_ZQ_K23") (pintype "passive"))
    )
    (net (code "265") (name "Net-(X4-X1)") (class "Default")
      (node (ref "C91") (pin "1") (pinfunction "1_1") (pintype "passive"))
      (node (ref "R71") (pin "2") (pinfunction "2_2") (pintype "passive"))
      (node (ref "X4") (pin "1") (pinfunction "X1_1") (pintype "passive"))
    )
    (net (code "266") (name "Net-(X6-EN)") (class "Default")
      (node (ref "C87") (pin "1") (pinfunction "1_1") (pintype "passive"))
      (node (ref "R302") (pin "1") (pinfunction "1_1") (pintype "passive"))
      (node (ref "R73") (pin "1") (pinfunction "1_1") (pintype "passive"))
      (node (ref "X6") (pin "1") (pinfunction "EN_1") (pintype "passive"))
    )
    (net (code "267") (name "Net-(X6-VDD)") (class "Default")
      (node (ref "C300") (pin "2") (pinfunction "2_2") (pintype "passive"))
      (node (ref "R304") (pin "2") (pinfunction "2_2") (pintype "passive"))
      (node (ref "X6") (pin "4") (pinfunction "VDD_4") (pintype "passive"))
    )
    (net (code "268") (name "VDD") (class "Default")
      (node (ref "R304") (pin "1") (pinfunction "1_1") (pintype "passive"))
      (node (ref "R5") (pin "1") (pinfunction "1_1") (pintype "passive"))
      (node (ref "R7") (pin "1") (pinfunction "1_1") (pintype "passive"))
      (node (ref "SB10") (pin "2") (pinfunction "2_2") (pintype "passive"))
      (node (ref "SB9") (pin "2") (pinfunction "2_2") (pintype "passive"))
    )
    (net (code "269") (name "VREF_DDR") (class "Default")
      (node (ref "C68") (pin "2") (pinfunction "2_2") (pintype "passive"))
      (node (ref "U13") (pin "AC20") (pinfunction "DDR_VREF_AC20") (pintype "passive"))
    )
    (net (code "270") (name "unconnected-(SB1-Pad1)") (class "Default")
      (node (ref "SB1") (pin "1") (pinfunction "1_1") (pintype "passive"))
    )
    (net (code "271") (name "unconnected-(SB2-Pad1)") (class "Default")
      (node (ref "SB2") (pin "1") (pinfunction "1_1") (pintype "passive"))
    )
    (net (code "272") (name "unconnected-(SB3-Pad1)") (class "Default")
      (node (ref "SB3") (pin "1") (pinfunction "1_1") (pintype "passive"))
    )
    (net (code "273") (name "unconnected-(SB4-Pad1)") (class "Default")
      (node (ref "SB4") (pin "1") (pinfunction "1_1") (pintype "passive"))
    )
    (net (code "274") (name "unconnected-(SB13-Pad1)") (class "Default")
      (node (ref "SB13") (pin "1") (pinfunction "1_1") (pintype "passive"))
    )
    (net (code "275") (name "unconnected-(SB14-Pad1)") (class "Default")
      (node (ref "SB14") (pin "1") (pinfunction "1_1") (pintype "passive"))
    )
    (net (code "276") (name "unconnected-(SB15-Pad1)") (class "Default")
      (node (ref "SB15") (pin "1") (pinfunction "1_1") (pintype "passive"))
    )
    (net (code "277") (name "unconnected-(SB16-Pad1)") (class "Default")
      (node (ref "SB16") (pin "1") (pinfunction "1_1") (pintype "passive"))
    )
    (net (code "278") (name "unconnected-(U13A-OTG_VBUS-PadAC19)") (class "Default")
      (node (ref "U13") (pin "AC19") (pinfunction "OTG_VBUS_AC19") (pintype "passive+no_connect"))
    )
    (net (code "279") (name "unconnected-(U13E-DDR_A15-PadP20)") (class "Default")
      (node (ref "U13") (pin "P20") (pinfunction "DDR_A15_P20") (pintype "passive+no_connect"))
    )
    (net (code "280") (name "unconnected-(U13E-DDR_DQ16-PadB22)") (class "Default")
      (node (ref "U13") (pin "B22") (pinfunction "DDR_DQ16_B22") (pintype "passive+no_connect"))
    )
    (net (code "281") (name "unconnected-(U13E-DDR_DQ17-PadD22)") (class "Default")
      (node (ref "U13") (pin "D22") (pinfunction "DDR_DQ17_D22") (pintype "passive+no_connect"))
    )
    (net (code "282") (name "unconnected-(U13E-DDR_DQ18-PadD23)") (class "Default")
      (node (ref "U13") (pin "D23") (pinfunction "DDR_DQ18_D23") (pintype "passive+no_connect"))
    )
    (net (code "283") (name "unconnected-(U13E-DDR_DQ19-PadB21)") (class "Default")
      (node (ref "U13") (pin "B21") (pinfunction "DDR_DQ19_B21") (pintype "passive+no_connect"))
    )
    (net (code "284") (name "unconnected-(U13E-DDR_DQ20-PadA21)") (class "Default")
      (node (ref "U13") (pin "A21") (pinfunction "DDR_DQ20_A21") (pintype "passive+no_connect"))
    )
    (net (code "285") (name "unconnected-(U13E-DDR_DQ21-PadE23)") (class "Default")
      (node (ref "U13") (pin "E23") (pinfunction "DDR_DQ21_E23") (pintype "passive+no_connect"))
    )
    (net (code "286") (name "unconnected-(U13E-DDR_DQ22-PadD21)") (class "Default")
      (node (ref "U13") (pin "D21") (pinfunction "DDR_DQ22_D21") (pintype "passive+no_connect"))
    )
    (net (code "287") (name "unconnected-(U13E-DDR_DQ23-PadA22)") (class "Default")
      (node (ref "U13") (pin "A22") (pinfunction "DDR_DQ23_A22") (pintype "passive+no_connect"))
    )
    (net (code "288") (name "unconnected-(U13E-DDR_DQ24-PadY23)") (class "Default")
      (node (ref "U13") (pin "Y23") (pinfunction "DDR_DQ24_Y23") (pintype "passive+no_connect"))
    )
    (net (code "289") (name "unconnected-(U13E-DDR_DQ25-PadY22)") (class "Default")
      (node (ref "U13") (pin "Y22") (pinfunction "DDR_DQ25_Y22") (pintype "passive+no_connect"))
    )
    (net (code "290") (name "unconnected-(U13E-DDR_DQ26-PadAB21)") (class "Default")
      (node (ref "U13") (pin "AB21") (pinfunction "DDR_DQ26_AB21") (pintype "passive+no_connect"))
    )
    (net (code "291") (name "unconnected-(U13E-DDR_DQ27-PadAB20)") (class "Default")
      (node (ref "U13") (pin "AB20") (pinfunction "DDR_DQ27_AB20") (pintype "passive+no_connect"))
    )
    (net (code "292") (name "unconnected-(U13E-DDR_DQ28-PadAC22)") (class "Default")
      (node (ref "U13") (pin "AC22") (pinfunction "DDR_DQ28_AC22") (pintype "passive+no_connect"))
    )
    (net (code "293") (name "unconnected-(U13E-DDR_DQ29-PadAC21)") (class "Default")
      (node (ref "U13") (pin "AC21") (pinfunction "DDR_DQ29_AC21") (pintype "passive+no_connect"))
    )
    (net (code "294") (name "unconnected-(U13E-DDR_DQ30-PadAA23)") (class "Default")
      (node (ref "U13") (pin "AA23") (pinfunction "DDR_DQ30_AA23") (pintype "passive+no_connect"))
    )
    (net (code "295") (name "unconnected-(U13E-DDR_DQ31-PadAA22)") (class "Default")
      (node (ref "U13") (pin "AA22") (pinfunction "DDR_DQ31_AA22") (pintype "passive+no_connect"))
    )
    (net (code "296") (name "unconnected-(U13E-DDR_DQM2-PadC23)") (class "Default")
      (node (ref "U13") (pin "C23") (pinfunction "DDR_DQM2_C23") (pintype "passive+no_connect"))
    )
    (net (code "297") (name "unconnected-(U13E-DDR_DQM3-PadAA20)") (class "Default")
      (node (ref "U13") (pin "AA20") (pinfunction "DDR_DQM3_AA20") (pintype "passive+no_connect"))
    )
    (net (code "298") (name "unconnected-(U13E-DDR_DQS2N-PadB23)") (class "Default")
      (node (ref "U13") (pin "B23") (pinfunction "DDR_DQS2N_B23") (pintype "passive+no_connect"))
    )
    (net (code "299") (name "unconnected-(U13E-DDR_DQS2P-PadC22)") (class "Default")
      (node (ref "U13") (pin "C22") (pinfunction "DDR_DQS2P_C22") (pintype "passive+no_connect"))
    )
    (net (code "300") (name "unconnected-(U13E-DDR_DQS3N-PadAB23)") (class "Default")
      (node (ref "U13") (pin "AB23") (pinfunction "DDR_DQS3N_AB23") (pintype "passive+no_connect"))
    )
    (net (code "301") (name "unconnected-(U13E-DDR_DQS3P-PadAB22)") (class "Default")
      (node (ref "U13") (pin "AB22") (pinfunction "DDR_DQS3P_AB22") (pintype "passive+no_connect"))
    )
  )
)
